# potenciostato_last.net
KiCad netlist of a schematic drawn in EAGLE
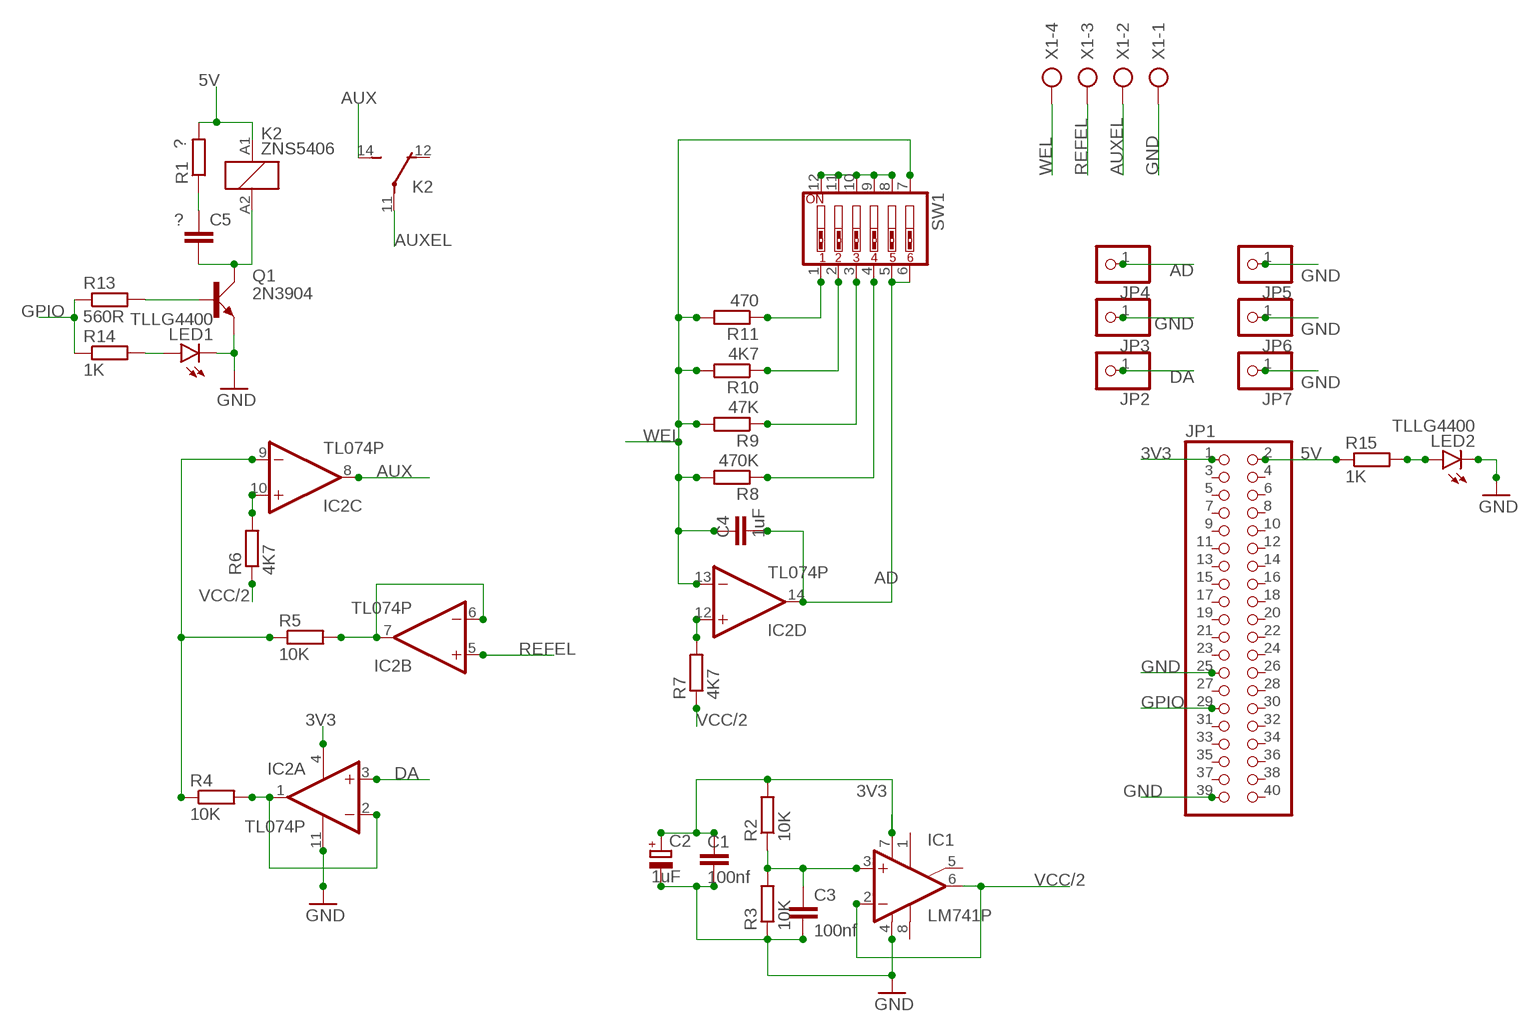
[diagram p0: schematic, sheet 1]

(export (version "E")
  (design (tool "Eeschema 10.0.6"))
  (components
    (comp (ref "C1")
      (value "100nf")
      (footprint "eagle-import:C050-035X075")
      (libsource (lib "eagle-import") (part "C-EU050-035X075"))
    )
    (comp (ref "C2")
      (value "1uF")
      (footprint "eagle-import:E2,5-5")
      (libsource (lib "eagle-import") (part "CPOL-EUE2.5-5"))
    )
    (comp (ref "C3")
      (value "100nf")
      (footprint "eagle-import:C050-035X075")
      (libsource (lib "eagle-import") (part "C-EU050-035X075"))
    )
    (comp (ref "C4")
      (value "1uF")
      (footprint "eagle-import:C050-035X075")
      (libsource (lib "eagle-import") (part "C-EU050-035X075"))
    )
    (comp (ref "C5")
      (value "?")
      (footprint "eagle-import:C050-035X075")
      (libsource (lib "eagle-import") (part "C-EU050-035X075"))
    )
    (comp (ref "IC1")
      (value "LM741P")
      (footprint "eagle-import:DIL08")
      (libsource (lib "eagle-import") (part "741PLM"))
    )
    (comp (ref "IC2")
      (value "TL074P")
      (footprint "eagle-import:DIL14")
      (libsource (lib "eagle-import") (part "TL074P"))
    )
    (comp (ref "JP1")
      (value "PINHD-2X20/90")
      (footprint "eagle-import:2X20_90")
      (libsource (lib "eagle-import") (part "PINHD-2X20/90"))
    )
    (comp (ref "JP2")
      (value "PINHD-1X1")
      (footprint "eagle-import:1X01")
      (libsource (lib "eagle-import") (part "PINHD-1X1"))
    )
    (comp (ref "JP3")
      (value "PINHD-1X1")
      (footprint "eagle-import:1X01")
      (libsource (lib "eagle-import") (part "PINHD-1X1"))
    )
    (comp (ref "JP4")
      (value "PINHD-1X1")
      (footprint "eagle-import:1X01")
      (libsource (lib "eagle-import") (part "PINHD-1X1"))
    )
    (comp (ref "JP5")
      (value "PINHD-1X1")
      (footprint "eagle-import:1X01")
      (libsource (lib "eagle-import") (part "PINHD-1X1"))
    )
    (comp (ref "JP6")
      (value "PINHD-1X1")
      (footprint "eagle-import:1X01")
      (libsource (lib "eagle-import") (part "PINHD-1X1"))
    )
    (comp (ref "JP7")
      (value "PINHD-1X1")
      (footprint "eagle-import:1X01")
      (libsource (lib "eagle-import") (part "PINHD-1X1"))
    )
    (comp (ref "K2")
      (value "ZNS5406")
      (footprint "eagle-import:ZN5")
      (libsource (lib "eagle-import") (part "ZNS5406"))
    )
    (comp (ref "LED1")
      (value "TLLG4400")
      (footprint "eagle-import:LED3MM")
      (fields (field (name "MF") "VISHAY SEMICONDUCTOR"))
      (libsource (lib "eagle-import") (part "TLLG4400"))
    )
    (comp (ref "LED2")
      (value "TLLG4400")
      (footprint "eagle-import:LED3MM")
      (fields (field (name "MF") "VISHAY SEMICONDUCTOR"))
      (libsource (lib "eagle-import") (part "TLLG4400"))
    )
    (comp (ref "Q1")
      (value "2N3904")
      (footprint "eagle-import:TO92D")
      (libsource (lib "eagle-import") (part "2N3904"))
    )
    (comp (ref "R1")
      (value "?")
      (footprint "eagle-import:0207_7")
      (libsource (lib "eagle-import") (part "R-EU_0207/7"))
    )
    (comp (ref "R2")
      (value "10K")
      (footprint "eagle-import:0207_7")
      (libsource (lib "eagle-import") (part "R-EU_0207/7"))
    )
    (comp (ref "R3")
      (value "10K")
      (footprint "eagle-import:0207_7")
      (libsource (lib "eagle-import") (part "R-EU_0207/7"))
    )
    (comp (ref "R4")
      (value "10K")
      (footprint "eagle-import:0207_7")
      (libsource (lib "eagle-import") (part "R-EU_0207/7"))
    )
    (comp (ref "R5")
      (value "10K")
      (footprint "eagle-import:0207_7")
      (libsource (lib "eagle-import") (part "R-EU_0207/7"))
    )
    (comp (ref "R6")
      (value "4K7")
      (footprint "eagle-import:0207_7")
      (libsource (lib "eagle-import") (part "R-EU_0207/7"))
    )
    (comp (ref "R7")
      (value "4K7")
      (footprint "eagle-import:0207_7")
      (libsource (lib "eagle-import") (part "R-EU_0207/7"))
    )
    (comp (ref "R8")
      (value "470K")
      (footprint "eagle-import:0207_7")
      (libsource (lib "eagle-import") (part "R-EU_0207/7"))
    )
    (comp (ref "R9")
      (value "47K")
      (footprint "eagle-import:0207_7")
      (libsource (lib "eagle-import") (part "R-EU_0207/7"))
    )
    (comp (ref "R10")
      (value "4K7")
      (footprint "eagle-import:0207_7")
      (libsource (lib "eagle-import") (part "R-EU_0207/7"))
    )
    (comp (ref "R11")
      (value "470")
      (footprint "eagle-import:0207_7")
      (libsource (lib "eagle-import") (part "R-EU_0207/7"))
    )
    (comp (ref "R13")
      (value "560R")
      (footprint "eagle-import:0207_7")
      (libsource (lib "eagle-import") (part "R-EU_0207/7"))
    )
    (comp (ref "R14")
      (value "1K")
      (footprint "eagle-import:0207_7")
      (libsource (lib "eagle-import") (part "R-EU_0207/7"))
    )
    (comp (ref "R15")
      (value "1K")
      (footprint "eagle-import:0207_7")
      (libsource (lib "eagle-import") (part "R-EU_0207/7"))
    )
    (comp (ref "SW1")
      (value "SW_DIP-6")
      (footprint "eagle-import:EDG-06")
      (libsource (lib "eagle-import") (part "SW_DIP-6"))
    )
    (comp (ref "X1")
      (value "AK500/4")
      (footprint "eagle-import:AK500_4")
      (libsource (lib "eagle-import") (part "AK500/4"))
    )
  )
  (nets
    (net (code "1") (name "/3V3") (class "Default")
      (node (ref "C1") (pin "1") (pinfunction "1_1") (pintype "passive"))
      (node (ref "C2") (pin "+") (pinfunction "+_+") (pintype "passive"))
      (node (ref "IC1") (pin "7") (pinfunction "V+_7") (pintype "power_in"))
      (node (ref "IC2") (pin "4") (pinfunction "V+_4") (pintype "power_in"))
      (node (ref "JP1") (pin "1") (pinfunction "1_1") (pintype "passive"))
      (node (ref "R2") (pin "2") (pinfunction "2_2") (pintype "passive"))
    )
    (net (code "2") (name "/5V") (class "Default")
      (node (ref "JP1") (pin "2") (pinfunction "2_2") (pintype "passive"))
      (node (ref "K2") (pin "A1") (pinfunction "1_A1") (pintype "passive"))
      (node (ref "R1") (pin "2") (pinfunction "2_2") (pintype "passive"))
      (node (ref "R15") (pin "1") (pinfunction "1_1") (pintype "passive"))
    )
    (net (code "3") (name "/AD") (class "Default")
      (node (ref "C4") (pin "2") (pinfunction "2_2") (pintype "passive"))
      (node (ref "IC2") (pin "14") (pinfunction "OUT_14") (pintype "output"))
      (node (ref "JP4") (pin "1") (pinfunction "1_1") (pintype "passive"))
      (node (ref "SW1") (pin "5") (pinfunction "5_5") (pintype "passive"))
      (node (ref "SW1") (pin "6") (pinfunction "6_6") (pintype "passive"))
    )
    (net (code "4") (name "/AUX") (class "Default")
      (node (ref "IC2") (pin "8") (pinfunction "OUT_8") (pintype "output"))
      (node (ref "K2") (pin "14") (pinfunction "S_14") (pintype "passive"))
    )
    (net (code "5") (name "/AUXEL") (class "Default")
      (node (ref "K2") (pin "11") (pinfunction "P_11") (pintype "passive"))
      (node (ref "X1") (pin "2") (pinfunction "KL_2") (pintype "passive"))
    )
    (net (code "6") (name "/DA") (class "Default")
      (node (ref "IC2") (pin "3") (pinfunction "+IN_3") (pintype "input"))
      (node (ref "JP2") (pin "1") (pinfunction "1_1") (pintype "passive"))
    )
    (net (code "7") (name "/GPIO") (class "Default")
      (node (ref "JP1") (pin "29") (pinfunction "29_29") (pintype "passive"))
      (node (ref "R13") (pin "1") (pinfunction "1_1") (pintype "passive"))
      (node (ref "R14") (pin "1") (pinfunction "1_1") (pintype "passive"))
    )
    (net (code "8") (name "/REFEL") (class "Default")
      (node (ref "IC2") (pin "5") (pinfunction "+IN_5") (pintype "input"))
      (node (ref "X1") (pin "3") (pinfunction "KL_3") (pintype "passive"))
    )
    (net (code "9") (name "/VCC{slash}2") (class "Default")
      (node (ref "IC1") (pin "2") (pinfunction "-IN_2") (pintype "input"))
      (node (ref "IC1") (pin "6") (pinfunction "OUT_6") (pintype "output"))
      (node (ref "R6") (pin "1") (pinfunction "1_1") (pintype "passive"))
      (node (ref "R7") (pin "1") (pinfunction "1_1") (pintype "passive"))
    )
    (net (code "10") (name "/WEL") (class "Default")
      (node (ref "C4") (pin "1") (pinfunction "1_1") (pintype "passive"))
      (node (ref "IC2") (pin "13") (pinfunction "-IN_13") (pintype "input"))
      (node (ref "R10") (pin "2") (pinfunction "2_2") (pintype "passive"))
      (node (ref "R11") (pin "2") (pinfunction "2_2") (pintype "passive"))
      (node (ref "R8") (pin "2") (pinfunction "2_2") (pintype "passive"))
      (node (ref "R9") (pin "2") (pinfunction "2_2") (pintype "passive"))
      (node (ref "SW1") (pin "7") (pinfunction "7_7") (pintype "passive"))
      (node (ref "X1") (pin "4") (pinfunction "KL_4") (pintype "passive"))
    )
    (net (code "11") (name "GND") (class "Default")
      (node (ref "C1") (pin "2") (pinfunction "2_2") (pintype "passive"))
      (node (ref "C2") (pin "-") (pinfunction "-_-") (pintype "passive"))
      (node (ref "C3") (pin "2") (pinfunction "2_2") (pintype "passive"))
      (node (ref "IC1") (pin "4") (pinfunction "V-_4") (pintype "power_in"))
      (node (ref "IC2") (pin "11") (pinfunction "V-_11") (pintype "power_in"))
      (node (ref "JP1") (pin "25") (pinfunction "25_25") (pintype "passive"))
      (node (ref "JP1") (pin "39") (pinfunction "39_39") (pintype "passive"))
      (node (ref "JP3") (pin "1") (pinfunction "1_1") (pintype "passive"))
      (node (ref "JP5") (pin "1") (pinfunction "1_1") (pintype "passive"))
      (node (ref "JP6") (pin "1") (pinfunction "1_1") (pintype "passive"))
      (node (ref "JP7") (pin "1") (pinfunction "1_1") (pintype "passive"))
      (node (ref "LED1") (pin "K") (pinfunction "C_K") (pintype "passive"))
      (node (ref "LED2") (pin "K") (pinfunction "C_K") (pintype "passive"))
      (node (ref "Q1") (pin "E") (pinfunction "E_E") (pintype "passive"))
      (node (ref "R3") (pin "1") (pinfunction "1_1") (pintype "passive"))
      (node (ref "X1") (pin "1") (pinfunction "KL_1") (pintype "passive"))
    )
    (net (code "12") (name "Net-(C5-Pad1)") (class "Default")
      (node (ref "C5") (pin "1") (pinfunction "1_1") (pintype "passive"))
      (node (ref "R1") (pin "1") (pinfunction "1_1") (pintype "passive"))
    )
    (net (code "13") (name "Net-(IC1-+IN)") (class "Default")
      (node (ref "C3") (pin "1") (pinfunction "1_1") (pintype "passive"))
      (node (ref "IC1") (pin "3") (pinfunction "+IN_3") (pintype "input"))
      (node (ref "R2") (pin "1") (pinfunction "1_1") (pintype "passive"))
      (node (ref "R3") (pin "2") (pinfunction "2_2") (pintype "passive"))
    )
    (net (code "14") (name "Net-(IC2A--IN)") (class "Default")
      (node (ref "IC2") (pin "1") (pinfunction "OUT_1") (pintype "output"))
      (node (ref "IC2") (pin "2") (pinfunction "-IN_2") (pintype "input"))
      (node (ref "R4") (pin "2") (pinfunction "2_2") (pintype "passive"))
    )
    (net (code "15") (name "Net-(IC2B--IN)") (class "Default")
      (node (ref "IC2") (pin "6") (pinfunction "-IN_6") (pintype "input"))
      (node (ref "IC2") (pin "7") (pinfunction "OUT_7") (pintype "output"))
      (node (ref "R5") (pin "2") (pinfunction "2_2") (pintype "passive"))
    )
    (net (code "16") (name "Net-(IC2C-+IN)") (class "Default")
      (node (ref "IC2") (pin "10") (pinfunction "+IN_10") (pintype "input"))
      (node (ref "R6") (pin "2") (pinfunction "2_2") (pintype "passive"))
    )
    (net (code "17") (name "Net-(IC2C--IN)") (class "Default")
      (node (ref "IC2") (pin "9") (pinfunction "-IN_9") (pintype "input"))
      (node (ref "R4") (pin "1") (pinfunction "1_1") (pintype "passive"))
      (node (ref "R5") (pin "1") (pinfunction "1_1") (pintype "passive"))
    )
    (net (code "18") (name "Net-(IC2D-+IN)") (class "Default")
      (node (ref "IC2") (pin "12") (pinfunction "+IN_12") (pintype "input"))
      (node (ref "R7") (pin "2") (pinfunction "2_2") (pintype "passive"))
    )
    (net (code "19") (name "Net-(K2A-2)") (class "Default")
      (node (ref "C5") (pin "2") (pinfunction "2_2") (pintype "passive"))
      (node (ref "K2") (pin "A2") (pinfunction "2_A2") (pintype "passive"))
      (node (ref "Q1") (pin "C") (pinfunction "C_C") (pintype "passive"))
    )
    (net (code "20") (name "Net-(LED1-PadA)") (class "Default")
      (node (ref "LED1") (pin "A") (pinfunction "A_A") (pintype "passive"))
      (node (ref "R14") (pin "2") (pinfunction "2_2") (pintype "passive"))
    )
    (net (code "21") (name "Net-(LED2-PadA)") (class "Default")
      (node (ref "LED2") (pin "A") (pinfunction "A_A") (pintype "passive"))
      (node (ref "R15") (pin "2") (pinfunction "2_2") (pintype "passive"))
    )
    (net (code "22") (name "Net-(Q1-PadB)") (class "Default")
      (node (ref "Q1") (pin "B") (pinfunction "B_B") (pintype "passive"))
      (node (ref "R13") (pin "2") (pinfunction "2_2") (pintype "passive"))
    )
    (net (code "23") (name "Net-(R8-Pad1)") (class "Default")
      (node (ref "R8") (pin "1") (pinfunction "1_1") (pintype "passive"))
      (node (ref "SW1") (pin "4") (pinfunction "4_4") (pintype "passive"))
    )
    (net (code "24") (name "Net-(R9-Pad1)") (class "Default")
      (node (ref "R9") (pin "1") (pinfunction "1_1") (pintype "passive"))
      (node (ref "SW1") (pin "3") (pinfunction "3_3") (pintype "passive"))
    )
    (net (code "25") (name "Net-(R10-Pad1)") (class "Default")
      (node (ref "R10") (pin "1") (pinfunction "1_1") (pintype "passive"))
      (node (ref "SW1") (pin "2") (pinfunction "2_2") (pintype "passive"))
    )
    (net (code "26") (name "Net-(R11-Pad1)") (class "Default")
      (node (ref "R11") (pin "1") (pinfunction "1_1") (pintype "passive"))
      (node (ref "SW1") (pin "1") (pinfunction "1_1") (pintype "passive"))
    )
    (net (code "27") (name "Net-(SW1-Pad10)") (class "Default")
      (node (ref "SW1") (pin "10") (pinfunction "10_10") (pintype "passive"))
      (node (ref "SW1") (pin "11") (pinfunction "11_11") (pintype "passive"))
      (node (ref "SW1") (pin "12") (pinfunction "12_12") (pintype "passive"))
      (node (ref "SW1") (pin "8") (pinfunction "8_8") (pintype "passive"))
      (node (ref "SW1") (pin "9") (pinfunction "9_9") (pintype "passive"))
    )
    (net (code "28") (name "unconnected-(IC1-ON1-Pad1)") (class "Default")
      (node (ref "IC1") (pin "1") (pinfunction "ON1_1") (pintype "passive"))
    )
    (net (code "29") (name "unconnected-(IC1-ON2-Pad5)") (class "Default")
      (node (ref "IC1") (pin "5") (pinfunction "ON2_5") (pintype "passive"))
    )
    (net (code "30") (name "unconnected-(IC1-OPT-Pad8)") (class "Default")
      (node (ref "IC1") (pin "8") (pinfunction "OPT_8") (pintype "passive"))
    )
    (net (code "31") (name "unconnected-(JP1-Pad3)") (class "Default")
      (node (ref "JP1") (pin "3") (pinfunction "3_3") (pintype "passive"))
    )
    (net (code "32") (name "unconnected-(JP1-Pad4)") (class "Default")
      (node (ref "JP1") (pin "4") (pinfunction "4_4") (pintype "passive"))
    )
    (net (code "33") (name "unconnected-(JP1-Pad5)") (class "Default")
      (node (ref "JP1") (pin "5") (pinfunction "5_5") (pintype "passive"))
    )
    (net (code "34") (name "unconnected-(JP1-Pad6)") (class "Default")
      (node (ref "JP1") (pin "6") (pinfunction "6_6") (pintype "passive"))
    )
    (net (code "35") (name "unconnected-(JP1-Pad7)") (class "Default")
      (node (ref "JP1") (pin "7") (pinfunction "7_7") (pintype "passive"))
    )
    (net (code "36") (name "unconnected-(JP1-Pad8)") (class "Default")
      (node (ref "JP1") (pin "8") (pinfunction "8_8") (pintype "passive"))
    )
    (net (code "37") (name "unconnected-(JP1-Pad9)") (class "Default")
      (node (ref "JP1") (pin "9") (pinfunction "9_9") (pintype "passive"))
    )
    (net (code "38") (name "unconnected-(JP1-Pad10)") (class "Default")
      (node (ref "JP1") (pin "10") (pinfunction "10_10") (pintype "passive"))
    )
    (net (code "39") (name "unconnected-(JP1-Pad11)") (class "Default")
      (node (ref "JP1") (pin "11") (pinfunction "11_11") (pintype "passive"))
    )
    (net (code "40") (name "unconnected-(JP1-Pad12)") (class "Default")
      (node (ref "JP1") (pin "12") (pinfunction "12_12") (pintype "passive"))
    )
    (net (code "41") (name "unconnected-(JP1-Pad13)") (class "Default")
      (node (ref "JP1") (pin "13") (pinfunction "13_13") (pintype "passive"))
    )
    (net (code "42") (name "unconnected-(JP1-Pad14)") (class "Default")
      (node (ref "JP1") (pin "14") (pinfunction "14_14") (pintype "passive"))
    )
    (net (code "43") (name "unconnected-(JP1-Pad15)") (class "Default")
      (node (ref "JP1") (pin "15") (pinfunction "15_15") (pintype "passive"))
    )
    (net (code "44") (name "unconnected-(JP1-Pad16)") (class "Default")
      (node (ref "JP1") (pin "16") (pinfunction "16_16") (pintype "passive"))
    )
    (net (code "45") (name "unconnected-(JP1-Pad17)") (class "Default")
      (node (ref "JP1") (pin "17") (pinfunction "17_17") (pintype "passive"))
    )
    (net (code "46") (name "unconnected-(JP1-Pad18)") (class "Default")
      (node (ref "JP1") (pin "18") (pinfunction "18_18") (pintype "passive"))
    )
    (net (code "47") (name "unconnected-(JP1-Pad19)") (class "Default")
      (node (ref "JP1") (pin "19") (pinfunction "19_19") (pintype "passive"))
    )
    (net (code "48") (name "unconnected-(JP1-Pad20)") (class "Default")
      (node (ref "JP1") (pin "20") (pinfunction "20_20") (pintype "passive"))
    )
    (net (code "49") (name "unconnected-(JP1-Pad21)") (class "Default")
      (node (ref "JP1") (pin "21") (pinfunction "21_21") (pintype "passive"))
    )
    (net (code "50") (name "unconnected-(JP1-Pad22)") (class "Default")
      (node (ref "JP1") (pin "22") (pinfunction "22_22") (pintype "passive"))
    )
    (net (code "51") (name "unconnected-(JP1-Pad23)") (class "Default")
      (node (ref "JP1") (pin "23") (pinfunction "23_23") (pintype "passive"))
    )
    (net (code "52") (name "unconnected-(JP1-Pad24)") (class "Default")
      (node (ref "JP1") (pin "24") (pinfunction "24_24") (pintype "passive"))
    )
    (net (code "53") (name "unconnected-(JP1-Pad26)") (class "Default")
      (node (ref "JP1") (pin "26") (pinfunction "26_26") (pintype "passive"))
    )
    (net (code "54") (name "unconnected-(JP1-Pad27)") (class "Default")
      (node (ref "JP1") (pin "27") (pinfunction "27_27") (pintype "passive"))
    )
    (net (code "55") (name "unconnected-(JP1-Pad28)") (class "Default")
      (node (ref "JP1") (pin "28") (pinfunction "28_28") (pintype "passive"))
    )
    (net (code "56") (name "unconnected-(JP1-Pad30)") (class "Default")
      (node (ref "JP1") (pin "30") (pinfunction "30_30") (pintype "passive"))
    )
    (net (code "57") (name "unconnected-(JP1-Pad31)") (class "Default")
      (node (ref "JP1") (pin "31") (pinfunction "31_31") (pintype "passive"))
    )
    (net (code "58") (name "unconnected-(JP1-Pad32)") (class "Default")
      (node (ref "JP1") (pin "32") (pinfunction "32_32") (pintype "passive"))
    )
    (net (code "59") (name "unconnected-(JP1-Pad33)") (class "Default")
      (node (ref "JP1") (pin "33") (pinfunction "33_33") (pintype "passive"))
    )
    (net (code "60") (name "unconnected-(JP1-Pad34)") (class "Default")
      (node (ref "JP1") (pin "34") (pinfunction "34_34") (pintype "passive"))
    )
    (net (code "61") (name "unconnected-(JP1-Pad35)") (class "Default")
      (node (ref "JP1") (pin "35") (pinfunction "35_35") (pintype "passive"))
    )
    (net (code "62") (name "unconnected-(JP1-Pad36)") (class "Default")
      (node (ref "JP1") (pin "36") (pinfunction "36_36") (pintype "passive"))
    )
    (net (code "63") (name "unconnected-(JP1-Pad37)") (class "Default")
      (node (ref "JP1") (pin "37") (pinfunction "37_37") (pintype "passive"))
    )
    (net (code "64") (name "unconnected-(JP1-Pad38)") (class "Default")
      (node (ref "JP1") (pin "38") (pinfunction "38_38") (pintype "passive"))
    )
    (net (code "65") (name "unconnected-(JP1-Pad40)") (class "Default")
      (node (ref "JP1") (pin "40") (pinfunction "40_40") (pintype "passive"))
    )
    (net (code "66") (name "unconnected-(K2B-O-Pad12)") (class "Default")
      (node (ref "K2") (pin "12") (pinfunction "O_12") (pintype "passive"))
    )
  )
)
